# Remote_Monitoring_Hardware.net
KiCad netlist of a schematic drawn in EAGLE
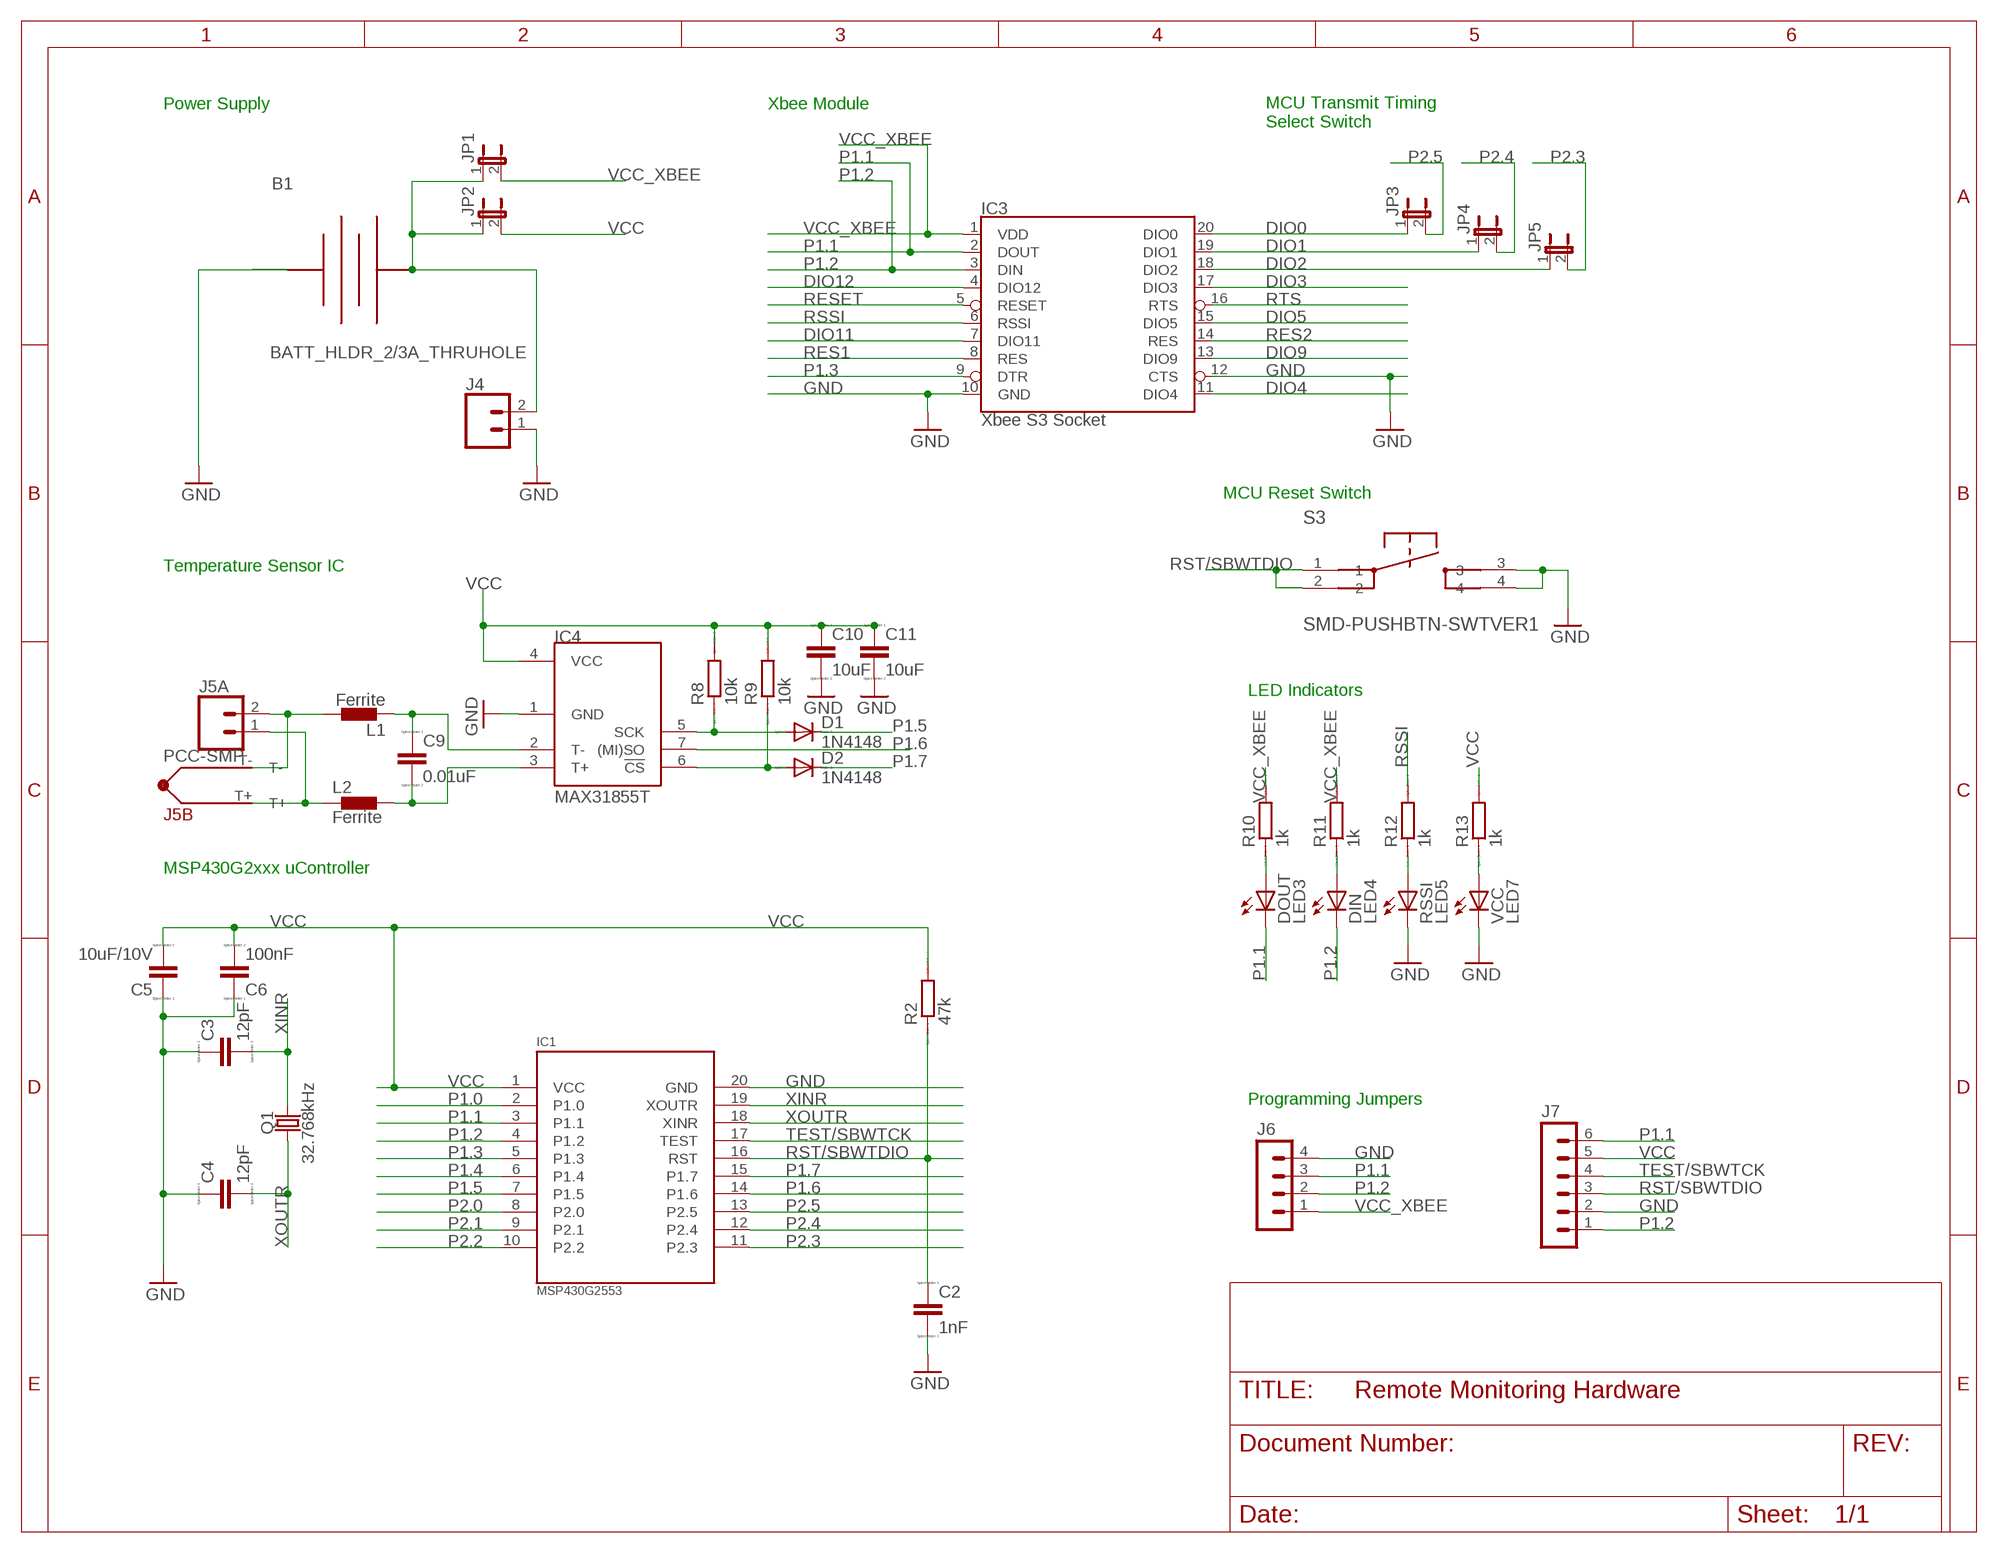
[diagram p0: schematic, sheet 1]

(export (version "E")
  (design (tool "Eeschema 10.0.6"))
  (components
    (comp (ref "B1")
      (value "BATT_HLDR_2/3A_THRUHOLE")
      (footprint "eagle-import:BATT_HLDR_2_3A_THRUHOLE")
      (libsource (lib "eagle-import") (part "BATT_HLDR_2/3A_THRUHOLE"))
    )
    (comp (ref "C2")
      (value "1nF")
      (footprint "eagle-import:C0805")
      (libsource (lib "eagle-import") (part "C"))
    )
    (comp (ref "C3")
      (value "12pF")
      (footprint "eagle-import:C0805")
      (libsource (lib "eagle-import") (part "C"))
    )
    (comp (ref "C4")
      (value "12pF")
      (footprint "eagle-import:C0805")
      (libsource (lib "eagle-import") (part "C"))
    )
    (comp (ref "C5")
      (value "10uF/10V")
      (footprint "eagle-import:C0805")
      (libsource (lib "eagle-import") (part "C"))
    )
    (comp (ref "C6")
      (value "100nF")
      (footprint "eagle-import:C0805")
      (libsource (lib "eagle-import") (part "C"))
    )
    (comp (ref "C9")
      (value "0.01uF")
      (footprint "eagle-import:C0805")
      (libsource (lib "eagle-import") (part "C"))
    )
    (comp (ref "C10")
      (value "10uF")
      (footprint "eagle-import:C0805")
      (libsource (lib "eagle-import") (part "C"))
    )
    (comp (ref "C11")
      (value "10uF")
      (footprint "eagle-import:C0805")
      (libsource (lib "eagle-import") (part "C"))
    )
    (comp (ref "D1")
      (value "1N4148")
      (footprint "eagle-import:SOD323-R")
      (libsource (lib "eagle-import") (part "DIODE-SOD323-R"))
    )
    (comp (ref "D2")
      (value "1N4148")
      (footprint "eagle-import:SOD323-R")
      (libsource (lib "eagle-import") (part "DIODE-SOD323-R"))
    )
    (comp (ref "DIN")
      (value "LED4")
      (footprint "eagle-import:SML0805")
      (libsource (lib "eagle-import") (part "LEDSML0805"))
    )
    (comp (ref "DOUT")
      (value "LED3")
      (footprint "eagle-import:SML0805")
      (libsource (lib "eagle-import") (part "LEDSML0805"))
    )
    (comp (ref "IC1")
      (value "MSP430G2553")
      (footprint "eagle-import:MSP430G2553IPW20")
      (libsource (lib "eagle-import") (part "MSP430G2553IPW20VER2TSSOP-20"))
    )
    (comp (ref "IC3")
      (value "Xbee S3 Socket")
      (footprint "eagle-import:XBEE-LONGPAD")
      (libsource (lib "eagle-import") (part "XBEELONGPAD"))
    )
    (comp (ref "IC4")
      (value "MAX31855T")
      (footprint "eagle-import:SOIC8")
      (libsource (lib "eagle-import") (part "MAX6675"))
    )
    (comp (ref "J4")
      (value "CONN_023.5MM")
      (footprint "eagle-import:SCREWTERMINAL-3.5MM-2")
      (libsource (lib "eagle-import") (part "CONN_023.5MM"))
    )
    (comp (ref "J5A")
      (value "CONN_023.5MM")
      (footprint "eagle-import:SCREWTERMINAL-3.5MM-2")
      (libsource (lib "eagle-import") (part "CONN_023.5MM"))
    )
    (comp (ref "J5B")
      (value "PCC-SMP")
      (footprint "eagle-import:PCC-SMP")
      (libsource (lib "eagle-import") (part "PCC-SMP"))
    )
    (comp (ref "J6")
      (value "MA04-1")
      (footprint "eagle-import:MA04-1")
      (libsource (lib "eagle-import") (part "MA04-1"))
    )
    (comp (ref "J7")
      (value "MA06-1")
      (footprint "eagle-import:MA06-1")
      (libsource (lib "eagle-import") (part "MA06-1"))
    )
    (comp (ref "JP1")
      (value "JUMPER-2PTH")
      (footprint "eagle-import:1X02")
      (libsource (lib "eagle-import") (part "JUMPER-2PTH"))
    )
    (comp (ref "JP2")
      (value "JUMPER-2PTH")
      (footprint "eagle-import:1X02")
      (libsource (lib "eagle-import") (part "JUMPER-2PTH"))
    )
    (comp (ref "JP3")
      (value "JUMPER-2PTH")
      (footprint "eagle-import:1X02")
      (libsource (lib "eagle-import") (part "JUMPER-2PTH"))
    )
    (comp (ref "JP4")
      (value "JUMPER-2PTH")
      (footprint "eagle-import:1X02")
      (libsource (lib "eagle-import") (part "JUMPER-2PTH"))
    )
    (comp (ref "JP5")
      (value "JUMPER-2PTH")
      (footprint "eagle-import:1X02")
      (libsource (lib "eagle-import") (part "JUMPER-2PTH"))
    )
    (comp (ref "L1")
      (value "Ferrite")
      (footprint "eagle-import:0402")
      (libsource (lib "eagle-import") (part "BLM15HB121SN1"))
    )
    (comp (ref "L2")
      (value "Ferrite")
      (footprint "eagle-import:0402")
      (libsource (lib "eagle-import") (part "BLM15HB121SN1"))
    )
    (comp (ref "Q1")
      (value "32.768kHz")
      (footprint "eagle-import:CRYSTAL-SMD-2X6-CYL")
      (libsource (lib "eagle-import") (part "CRYSTAL-32.768KHZSMD-2X6"))
    )
    (comp (ref "R2")
      (value "47k")
      (footprint "eagle-import:R0805")
      (libsource (lib "eagle-import") (part "R"))
    )
    (comp (ref "R8")
      (value "10k")
      (footprint "eagle-import:R0805")
      (libsource (lib "eagle-import") (part "R"))
    )
    (comp (ref "R9")
      (value "10k")
      (footprint "eagle-import:R0805")
      (libsource (lib "eagle-import") (part "R"))
    )
    (comp (ref "R10")
      (value "1k")
      (footprint "eagle-import:R0805")
      (libsource (lib "eagle-import") (part "R"))
    )
    (comp (ref "R11")
      (value "1k")
      (footprint "eagle-import:R0805")
      (libsource (lib "eagle-import") (part "R"))
    )
    (comp (ref "R12")
      (value "1k")
      (footprint "eagle-import:R0805")
      (libsource (lib "eagle-import") (part "R"))
    )
    (comp (ref "R13")
      (value "1k")
      (footprint "eagle-import:R0805")
      (libsource (lib "eagle-import") (part "R"))
    )
    (comp (ref "RSSI")
      (value "LED5")
      (footprint "eagle-import:SML0805")
      (libsource (lib "eagle-import") (part "LEDSML0805"))
    )
    (comp (ref "S3")
      (value "SMD-PUSHBTN-SWTVER1")
      (footprint "eagle-import:KPT-1187B")
      (libsource (lib "eagle-import") (part "SMD-PUSHBTN-SWTVER1"))
    )
    (comp (ref "VCC")
      (value "LED7")
      (footprint "eagle-import:SML0805")
      (libsource (lib "eagle-import") (part "LEDSML0805"))
    )
  )
  (nets
    (net (code "1") (name "/DIO0") (class "Default")
      (node (ref "IC3") (pin "20") (pinfunction "DIO0_20") (pintype "bidirectional"))
      (node (ref "JP3") (pin "1") (pinfunction "1_1") (pintype "passive"))
    )
    (net (code "2") (name "/DIO1") (class "Default")
      (node (ref "IC3") (pin "19") (pinfunction "DIO1_19") (pintype "bidirectional"))
      (node (ref "JP4") (pin "1") (pinfunction "1_1") (pintype "passive"))
    )
    (net (code "3") (name "/DIO2") (class "Default")
      (node (ref "IC3") (pin "18") (pinfunction "DIO2_18") (pintype "bidirectional"))
      (node (ref "JP5") (pin "1") (pinfunction "1_1") (pintype "passive"))
    )
    (net (code "4") (name "/DIO3") (class "Default")
      (node (ref "IC3") (pin "17") (pinfunction "DIO3_17") (pintype "bidirectional"))
    )
    (net (code "5") (name "/DIO4") (class "Default")
      (node (ref "IC3") (pin "11") (pinfunction "DIO4_11") (pintype "bidirectional"))
    )
    (net (code "6") (name "/DIO5") (class "Default")
      (node (ref "IC3") (pin "15") (pinfunction "DIO5_15") (pintype "bidirectional"))
    )
    (net (code "7") (name "/DIO9") (class "Default")
      (node (ref "IC3") (pin "13") (pinfunction "DIO9_13") (pintype "bidirectional"))
    )
    (net (code "8") (name "/DIO11") (class "Default")
      (node (ref "IC3") (pin "7") (pinfunction "DIO11_7") (pintype "bidirectional"))
    )
    (net (code "9") (name "/DIO12") (class "Default")
      (node (ref "IC3") (pin "4") (pinfunction "DIO12_4") (pintype "bidirectional"))
    )
    (net (code "10") (name "/P1.0") (class "Default")
      (node (ref "IC1") (pin "2") (pinfunction "P1.0_2") (pintype "bidirectional"))
    )
    (net (code "11") (name "/P1.1") (class "Default")
      (node (ref "DOUT") (pin "C") (pinfunction "C_C") (pintype "passive"))
      (node (ref "IC1") (pin "3") (pinfunction "P1.1_3") (pintype "bidirectional"))
      (node (ref "IC3") (pin "2") (pinfunction "DOUT_2") (pintype "output"))
      (node (ref "J6") (pin "3") (pinfunction "3_3") (pintype "passive"))
      (node (ref "J7") (pin "6") (pinfunction "6_6") (pintype "passive"))
    )
    (net (code "12") (name "/P1.2") (class "Default")
      (node (ref "DIN") (pin "C") (pinfunction "C_C") (pintype "passive"))
      (node (ref "IC1") (pin "4") (pinfunction "P1.2_4") (pintype "bidirectional"))
      (node (ref "IC3") (pin "3") (pinfunction "DIN_3") (pintype "input"))
      (node (ref "J6") (pin "2") (pinfunction "2_2") (pintype "passive"))
      (node (ref "J7") (pin "1") (pinfunction "1_1") (pintype "passive"))
    )
    (net (code "13") (name "/P1.3") (class "Default")
      (node (ref "IC1") (pin "5") (pinfunction "P1.3_5") (pintype "bidirectional"))
      (node (ref "IC3") (pin "9") (pinfunction "DTR_9") (pintype "bidirectional"))
    )
    (net (code "14") (name "/P1.4") (class "Default")
      (node (ref "IC1") (pin "6") (pinfunction "P1.4_6") (pintype "bidirectional"))
    )
    (net (code "15") (name "/P1.5") (class "Default")
      (node (ref "D1") (pin "C") (pinfunction "C_C") (pintype "passive"))
      (node (ref "IC1") (pin "7") (pinfunction "P1.5_7") (pintype "bidirectional"))
    )
    (net (code "16") (name "/P1.6") (class "Default")
      (node (ref "IC1") (pin "14") (pinfunction "P1.6_14") (pintype "bidirectional"))
      (node (ref "IC4") (pin "7") (pinfunction "(MI)SO_7") (pintype "bidirectional"))
    )
    (net (code "17") (name "/P1.7") (class "Default")
      (node (ref "D2") (pin "C") (pinfunction "C_C") (pintype "passive"))
      (node (ref "IC1") (pin "15") (pinfunction "P1.7_15") (pintype "bidirectional"))
    )
    (net (code "18") (name "/P2.0") (class "Default")
      (node (ref "IC1") (pin "8") (pinfunction "P2.0_8") (pintype "bidirectional"))
    )
    (net (code "19") (name "/P2.1") (class "Default")
      (node (ref "IC1") (pin "9") (pinfunction "P2.1_9") (pintype "bidirectional"))
    )
    (net (code "20") (name "/P2.2") (class "Default")
      (node (ref "IC1") (pin "10") (pinfunction "P2.2_10") (pintype "bidirectional"))
    )
    (net (code "21") (name "/P2.3") (class "Default")
      (node (ref "IC1") (pin "11") (pinfunction "P2.3_11") (pintype "bidirectional"))
      (node (ref "JP5") (pin "2") (pinfunction "2_2") (pintype "passive"))
    )
    (net (code "22") (name "/P2.4") (class "Default")
      (node (ref "IC1") (pin "12") (pinfunction "P2.4_12") (pintype "bidirectional"))
      (node (ref "JP4") (pin "2") (pinfunction "2_2") (pintype "passive"))
    )
    (net (code "23") (name "/P2.5") (class "Default")
      (node (ref "IC1") (pin "13") (pinfunction "P2.5_13") (pintype "bidirectional"))
      (node (ref "JP3") (pin "2") (pinfunction "2_2") (pintype "passive"))
    )
    (net (code "24") (name "/RES1") (class "Default")
      (node (ref "IC3") (pin "8") (pinfunction "RES_8") (pintype "bidirectional"))
    )
    (net (code "25") (name "/RES2") (class "Default")
      (node (ref "IC3") (pin "14") (pinfunction "RES_14") (pintype "bidirectional"))
    )
    (net (code "26") (name "/RESET") (class "Default")
      (node (ref "IC3") (pin "5") (pinfunction "RESET_5") (pintype "input"))
    )
    (net (code "27") (name "/RSSI") (class "Default")
      (node (ref "IC3") (pin "6") (pinfunction "RSSI_6") (pintype "bidirectional"))
      (node (ref "R12") (pin "2") (pinfunction "2_2") (pintype "passive"))
    )
    (net (code "28") (name "/RST{slash}SBWTDIO") (class "Default")
      (node (ref "C2") (pin "1") (pinfunction "1_1") (pintype "passive"))
      (node (ref "IC1") (pin "16") (pinfunction "RST_16") (pintype "bidirectional"))
      (node (ref "J7") (pin "3") (pinfunction "3_3") (pintype "passive"))
      (node (ref "R2") (pin "1") (pinfunction "1_1") (pintype "passive"))
      (node (ref "S3") (pin "1") (pinfunction "1_1") (pintype "bidirectional"))
      (node (ref "S3") (pin "2") (pinfunction "2_2") (pintype "bidirectional"))
    )
    (net (code "29") (name "/RTS") (class "Default")
      (node (ref "IC3") (pin "16") (pinfunction "RTS_16") (pintype "input"))
    )
    (net (code "30") (name "/TEST{slash}SBWTCK") (class "Default")
      (node (ref "IC1") (pin "17") (pinfunction "TEST_17") (pintype "bidirectional"))
      (node (ref "J7") (pin "4") (pinfunction "4_4") (pintype "passive"))
    )
    (net (code "31") (name "/VCC") (class "Default")
      (node (ref "C10") (pin "1") (pinfunction "1_1") (pintype "passive"))
      (node (ref "C11") (pin "1") (pinfunction "1_1") (pintype "passive"))
      (node (ref "C5") (pin "2") (pinfunction "2_2") (pintype "passive"))
      (node (ref "C6") (pin "2") (pinfunction "2_2") (pintype "passive"))
      (node (ref "IC1") (pin "1") (pinfunction "VCC_1") (pintype "power_in"))
      (node (ref "IC4") (pin "4") (pinfunction "VCC_4") (pintype "bidirectional"))
      (node (ref "J7") (pin "5") (pinfunction "5_5") (pintype "passive"))
      (node (ref "JP2") (pin "2") (pinfunction "2_2") (pintype "passive"))
      (node (ref "R13") (pin "2") (pinfunction "2_2") (pintype "passive"))
      (node (ref "R2") (pin "2") (pinfunction "2_2") (pintype "passive"))
      (node (ref "R8") (pin "2") (pinfunction "2_2") (pintype "passive"))
      (node (ref "R9") (pin "2") (pinfunction "2_2") (pintype "passive"))
    )
    (net (code "32") (name "/VCC_XBEE") (class "Default")
      (node (ref "IC3") (pin "1") (pinfunction "VDD_1") (pintype "power_in"))
      (node (ref "J6") (pin "1") (pinfunction "1_1") (pintype "passive"))
      (node (ref "JP1") (pin "2") (pinfunction "2_2") (pintype "passive"))
      (node (ref "R10") (pin "2") (pinfunction "2_2") (pintype "passive"))
      (node (ref "R11") (pin "2") (pinfunction "2_2") (pintype "passive"))
    )
    (net (code "33") (name "/XINR") (class "Default")
      (node (ref "C3") (pin "2") (pinfunction "2_2") (pintype "passive"))
      (node (ref "IC1") (pin "19") (pinfunction "XOUTR_19") (pintype "bidirectional"))
      (node (ref "Q1") (pin "X2") (pinfunction "2_X2") (pintype "passive"))
    )
    (net (code "34") (name "/XOUTR") (class "Default")
      (node (ref "C4") (pin "2") (pinfunction "2_2") (pintype "passive"))
      (node (ref "IC1") (pin "18") (pinfunction "XINR_18") (pintype "bidirectional"))
      (node (ref "Q1") (pin "X1") (pinfunction "1_X1") (pintype "passive"))
    )
    (net (code "35") (name "GND") (class "Default")
      (node (ref "B1") (pin "NEG") (pinfunction "NEG_NEG") (pintype "power_in"))
      (node (ref "C10") (pin "2") (pinfunction "2_2") (pintype "passive"))
      (node (ref "C11") (pin "2") (pinfunction "2_2") (pintype "passive"))
      (node (ref "C2") (pin "2") (pinfunction "2_2") (pintype "passive"))
      (node (ref "C3") (pin "1") (pinfunction "1_1") (pintype "passive"))
      (node (ref "C4") (pin "1") (pinfunction "1_1") (pintype "passive"))
      (node (ref "C5") (pin "1") (pinfunction "1_1") (pintype "passive"))
      (node (ref "C6") (pin "1") (pinfunction "1_1") (pintype "passive"))
      (node (ref "IC1") (pin "20") (pinfunction "GND_20") (pintype "power_in"))
      (node (ref "IC3") (pin "10") (pinfunction "GND_10") (pintype "power_in"))
      (node (ref "IC3") (pin "12") (pinfunction "CTS_12") (pintype "output"))
      (node (ref "IC4") (pin "1") (pinfunction "GND_1") (pintype "bidirectional"))
      (node (ref "J4") (pin "1") (pinfunction "1_1") (pintype "passive"))
      (node (ref "J6") (pin "4") (pinfunction "4_4") (pintype "passive"))
      (node (ref "J7") (pin "2") (pinfunction "2_2") (pintype "passive"))
      (node (ref "RSSI") (pin "C") (pinfunction "C_C") (pintype "passive"))
      (node (ref "S3") (pin "3") (pinfunction "3_3") (pintype "bidirectional"))
      (node (ref "S3") (pin "4") (pinfunction "4_4") (pintype "bidirectional"))
      (node (ref "VCC") (pin "C") (pinfunction "C_C") (pintype "passive"))
    )
    (net (code "36") (name "Net-(B1-PadPOS)") (class "Default")
      (node (ref "B1") (pin "POS") (pinfunction "POS_POS") (pintype "power_in"))
      (node (ref "J4") (pin "2") (pinfunction "2_2") (pintype "passive"))
      (node (ref "JP1") (pin "1") (pinfunction "1_1") (pintype "passive"))
      (node (ref "JP2") (pin "1") (pinfunction "1_1") (pintype "passive"))
    )
    (net (code "37") (name "Net-(DIN-PadA)") (class "Default")
      (node (ref "DIN") (pin "A") (pinfunction "A_A") (pintype "passive"))
      (node (ref "R11") (pin "1") (pinfunction "1_1") (pintype "passive"))
    )
    (net (code "38") (name "Net-(DOUT-PadA)") (class "Default")
      (node (ref "DOUT") (pin "A") (pinfunction "A_A") (pintype "passive"))
      (node (ref "R10") (pin "1") (pinfunction "1_1") (pintype "passive"))
    )
    (net (code "39") (name "Net-(IC4-SCK)") (class "Default")
      (node (ref "D1") (pin "A") (pinfunction "A_A") (pintype "passive"))
      (node (ref "IC4") (pin "5") (pinfunction "SCK_5") (pintype "bidirectional"))
      (node (ref "R8") (pin "1") (pinfunction "1_1") (pintype "passive"))
    )
    (net (code "40") (name "Net-(IC4-T+)") (class "Default")
      (node (ref "C9") (pin "2") (pinfunction "2_2") (pintype "passive"))
      (node (ref "IC4") (pin "3") (pinfunction "T+_3") (pintype "bidirectional"))
      (node (ref "L2") (pin "2") (pinfunction "2_2") (pintype "passive"))
    )
    (net (code "41") (name "Net-(IC4-T-)") (class "Default")
      (node (ref "C9") (pin "1") (pinfunction "1_1") (pintype "passive"))
      (node (ref "IC4") (pin "2") (pinfunction "T-_2") (pintype "bidirectional"))
      (node (ref "L1") (pin "1") (pinfunction "1_1") (pintype "passive"))
    )
    (net (code "42") (name "Net-(IC4-~{CS})") (class "Default")
      (node (ref "D2") (pin "A") (pinfunction "A_A") (pintype "passive"))
      (node (ref "IC4") (pin "6") (pinfunction "~{CS}_6") (pintype "bidirectional"))
      (node (ref "R9") (pin "1") (pinfunction "1_1") (pintype "passive"))
    )
    (net (code "43") (name "Net-(J5A-Pad1)") (class "Default")
      (node (ref "J5A") (pin "1") (pinfunction "1_1") (pintype "passive"))
      (node (ref "J5B") (pin "T+") (pinfunction "T+_T+") (pintype "bidirectional"))
      (node (ref "L2") (pin "1") (pinfunction "1_1") (pintype "passive"))
    )
    (net (code "44") (name "Net-(J5A-Pad2)") (class "Default")
      (node (ref "J5A") (pin "2") (pinfunction "2_2") (pintype "passive"))
      (node (ref "J5B") (pin "T-") (pinfunction "T-_T-") (pintype "bidirectional"))
      (node (ref "L1") (pin "2") (pinfunction "2_2") (pintype "passive"))
    )
    (net (code "45") (name "Net-(R12-Pad1)") (class "Default")
      (node (ref "R12") (pin "1") (pinfunction "1_1") (pintype "passive"))
      (node (ref "RSSI") (pin "A") (pinfunction "A_A") (pintype "passive"))
    )
    (net (code "46") (name "Net-(R13-Pad1)") (class "Default")
      (node (ref "R13") (pin "1") (pinfunction "1_1") (pintype "passive"))
      (node (ref "VCC") (pin "A") (pinfunction "A_A") (pintype "passive"))
    )
  )
)
